# SMD.net
KiCad netlist of a schematic drawn in EAGLE
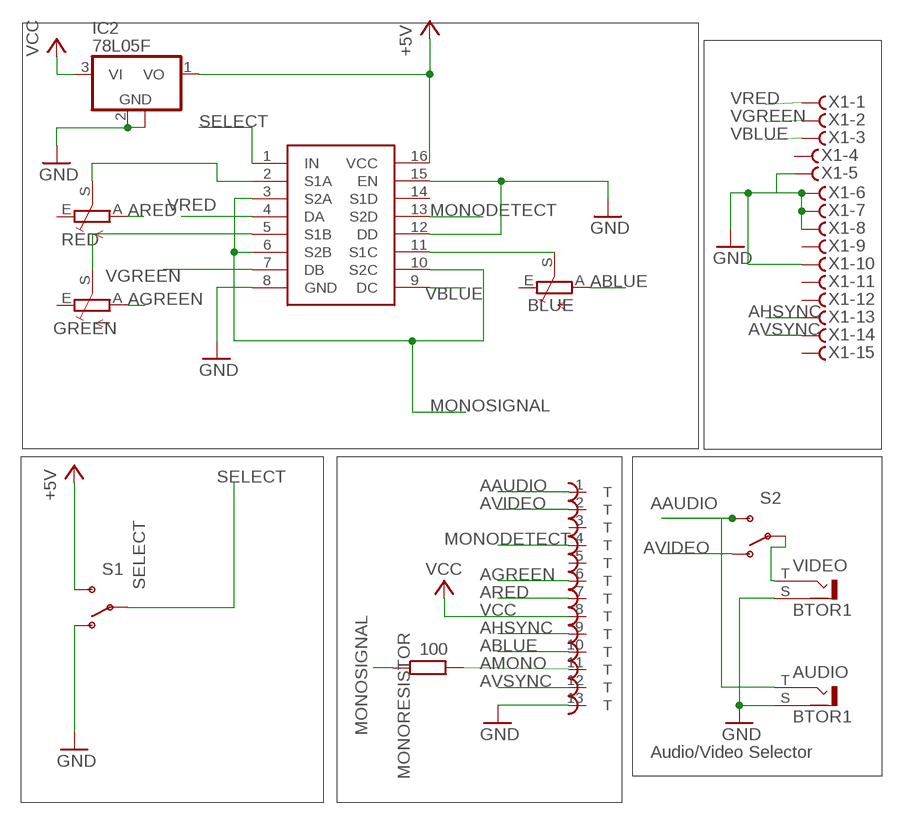
[diagram p0: schematic, sheet 1]

(export (version "E")
  (design (tool "Eeschema 10.0.6"))
  (components
    (comp (ref "ATARIOUT")
      (value "DIN13T")
      (footprint "eagle-import:ADADS")
      (libsource (lib "eagle-import") (part "DIN13T"))
    )
    (comp (ref "AUDIO")
      (value "BTOR1")
      (footprint "eagle-import:BTOR1")
      (libsource (lib "eagle-import") (part "BTOR1"))
    )
    (comp (ref "BLUE")
      (value "TRIM_EU-CA6H")
      (footprint "eagle-import:CA6H")
      (libsource (lib "eagle-import") (part "TRIM_EU-CA6H"))
    )
    (comp (ref "GREEN")
      (value "TRIM_EU-CA6H")
      (footprint "eagle-import:CA6H")
      (libsource (lib "eagle-import") (part "TRIM_EU-CA6H"))
    )
    (comp (ref "IC2")
      (value "78L05F")
      (footprint "eagle-import:SOT89")
      (libsource (lib "eagle-import") (part "78LF05"))
    )
    (comp (ref "MONORESISTOR")
      (value "100")
      (footprint "eagle-import:R1206")
      (libsource (lib "eagle-import") (part "R-EU_R1206"))
    )
    (comp (ref "RED")
      (value "TRIM_EU-CA6H")
      (footprint "eagle-import:CA6H")
      (libsource (lib "eagle-import") (part "TRIM_EU-CA6H"))
    )
    (comp (ref "S1")
      (value "SWITCH-SPDT-SMD-A")
      (footprint "eagle-import:SWITCH-SPST-SMD-A")
      (libsource (lib "eagle-import") (part "SWITCH-SPDT-SMD-A"))
    )
    (comp (ref "S2")
      (value "SWITCH-SPDT-SMD-A")
      (footprint "eagle-import:SWITCH-SPST-SMD-A")
      (libsource (lib "eagle-import") (part "SWITCH-SPDT-SMD-A"))
    )
    (comp (ref "TS5V330")
      (value "V330")
      (footprint "eagle-import:SOIC16N")
      (libsource (lib "eagle-import") (part "V330"))
    )
    (comp (ref "VIDEO")
      (value "BTOR1")
      (footprint "eagle-import:BTOR1")
      (libsource (lib "eagle-import") (part "BTOR1"))
    )
    (comp (ref "X1")
      (value "F15HDVS")
      (footprint "eagle-import:HDF15V")
      (libsource (lib "eagle-import") (part "F15?SHDV"))
    )
  )
  (nets
    (net (code "1") (name "+5V") (class "Default")
      (node (ref "IC2") (pin "1") (pinfunction "VO_1") (pintype "passive"))
      (node (ref "S1") (pin "3") (pinfunction "S_3") (pintype "passive"))
      (node (ref "TS5V330") (pin "16") (pinfunction "VCC_16") (pintype "bidirectional"))
    )
    (net (code "2") (name "/AAUDIO") (class "Default")
      (node (ref "ATARIOUT") (pin "1") (pinfunction "T_1") (pintype "passive"))
      (node (ref "AUDIO") (pin "T") (pinfunction "1_T") (pintype "passive"))
      (node (ref "S2") (pin "3") (pinfunction "S_3") (pintype "passive"))
    )
    (net (code "3") (name "/ABLUE") (class "Default")
      (node (ref "ATARIOUT") (pin "10") (pinfunction "T_10") (pintype "passive"))
      (node (ref "BLUE") (pin "A") (pinfunction "A_A") (pintype "passive"))
    )
    (net (code "4") (name "/AGREEN") (class "Default")
      (node (ref "ATARIOUT") (pin "6") (pinfunction "T_6") (pintype "passive"))
      (node (ref "GREEN") (pin "A") (pinfunction "A_A") (pintype "passive"))
    )
    (net (code "5") (name "/AHSYNC") (class "Default")
      (node (ref "ATARIOUT") (pin "9") (pinfunction "T_9") (pintype "passive"))
      (node (ref "X1") (pin "13") (pinfunction "F_13") (pintype "passive"))
    )
    (net (code "6") (name "/AMONO") (class "Default")
      (node (ref "ATARIOUT") (pin "11") (pinfunction "T_11") (pintype "passive"))
      (node (ref "MONORESISTOR") (pin "2") (pinfunction "2_2") (pintype "passive"))
    )
    (net (code "7") (name "/ARED") (class "Default")
      (node (ref "ATARIOUT") (pin "7") (pinfunction "T_7") (pintype "passive"))
      (node (ref "RED") (pin "A") (pinfunction "A_A") (pintype "passive"))
    )
    (net (code "8") (name "/AVIDEO") (class "Default")
      (node (ref "ATARIOUT") (pin "2") (pinfunction "T_2") (pintype "passive"))
      (node (ref "S2") (pin "1") (pinfunction "O_1") (pintype "passive"))
    )
    (net (code "9") (name "/AVSYNC") (class "Default")
      (node (ref "ATARIOUT") (pin "12") (pinfunction "T_12") (pintype "passive"))
      (node (ref "X1") (pin "14") (pinfunction "F_14") (pintype "passive"))
    )
    (net (code "10") (name "/MONODETECT") (class "Default")
      (node (ref "ATARIOUT") (pin "4") (pinfunction "T_4") (pintype "passive"))
      (node (ref "TS5V330") (pin "13") (pinfunction "S2D_13") (pintype "bidirectional"))
    )
    (net (code "11") (name "/MONOSIGNAL") (class "Default")
      (node (ref "MONORESISTOR") (pin "1") (pinfunction "1_1") (pintype "passive"))
      (node (ref "TS5V330") (pin "10") (pinfunction "S2C_10") (pintype "bidirectional"))
      (node (ref "TS5V330") (pin "3") (pinfunction "S2A_3") (pintype "bidirectional"))
      (node (ref "TS5V330") (pin "6") (pinfunction "S2B_6") (pintype "bidirectional"))
    )
    (net (code "12") (name "/SELECT") (class "Default")
      (node (ref "S1") (pin "2") (pinfunction "P_2") (pintype "passive"))
      (node (ref "TS5V330") (pin "1") (pinfunction "IN_1") (pintype "bidirectional"))
    )
    (net (code "13") (name "/VBLUE") (class "Default")
      (node (ref "TS5V330") (pin "9") (pinfunction "DC_9") (pintype "bidirectional"))
      (node (ref "X1") (pin "3") (pinfunction "F_3") (pintype "passive"))
    )
    (net (code "14") (name "/VGREEN") (class "Default")
      (node (ref "TS5V330") (pin "7") (pinfunction "DB_7") (pintype "bidirectional"))
      (node (ref "X1") (pin "2") (pinfunction "F_2") (pintype "passive"))
    )
    (net (code "15") (name "/VRED") (class "Default")
      (node (ref "TS5V330") (pin "4") (pinfunction "DA_4") (pintype "bidirectional"))
      (node (ref "X1") (pin "1") (pinfunction "F_1") (pintype "passive"))
    )
    (net (code "16") (name "GND") (class "Default")
      (node (ref "ATARIOUT") (pin "13") (pinfunction "T_13") (pintype "passive"))
      (node (ref "AUDIO") (pin "S") (pinfunction "2_S") (pintype "passive"))
      (node (ref "IC2") (pin "2") (pinfunction "GND_2") (pintype "passive"))
      (node (ref "IC2") (pin "2@1") (pinfunction "GND_2@1") (pintype "passive"))
      (node (ref "S1") (pin "1") (pinfunction "O_1") (pintype "passive"))
      (node (ref "TS5V330") (pin "12") (pinfunction "DD_12") (pintype "bidirectional"))
      (node (ref "TS5V330") (pin "15") (pinfunction "EN_15") (pintype "bidirectional"))
      (node (ref "TS5V330") (pin "8") (pinfunction "GND_8") (pintype "bidirectional"))
      (node (ref "VIDEO") (pin "S") (pinfunction "2_S") (pintype "passive"))
      (node (ref "X1") (pin "10") (pinfunction "F_10") (pintype "passive"))
      (node (ref "X1") (pin "5") (pinfunction "F_5") (pintype "passive"))
      (node (ref "X1") (pin "6") (pinfunction "F_6") (pintype "passive"))
      (node (ref "X1") (pin "7") (pinfunction "F_7") (pintype "passive"))
      (node (ref "X1") (pin "8") (pinfunction "F_8") (pintype "passive"))
    )
    (net (code "17") (name "Net-(S2-P)") (class "Default")
      (node (ref "S2") (pin "2") (pinfunction "P_2") (pintype "passive"))
      (node (ref "VIDEO") (pin "T") (pinfunction "1_T") (pintype "passive"))
    )
    (net (code "18") (name "Net-(TS5V330-S1A)") (class "Default")
      (node (ref "RED") (pin "S") (pinfunction "S_S") (pintype "passive"))
      (node (ref "TS5V330") (pin "2") (pinfunction "S1A_2") (pintype "bidirectional"))
    )
    (net (code "19") (name "Net-(TS5V330-S1B)") (class "Default")
      (node (ref "GREEN") (pin "S") (pinfunction "S_S") (pintype "passive"))
      (node (ref "TS5V330") (pin "5") (pinfunction "S1B_5") (pintype "bidirectional"))
    )
    (net (code "20") (name "Net-(TS5V330-S1C)") (class "Default")
      (node (ref "BLUE") (pin "S") (pinfunction "S_S") (pintype "passive"))
      (node (ref "TS5V330") (pin "11") (pinfunction "S1C_11") (pintype "bidirectional"))
    )
    (net (code "21") (name "VCC") (class "Default")
      (node (ref "ATARIOUT") (pin "8") (pinfunction "T_8") (pintype "passive"))
      (node (ref "IC2") (pin "3") (pinfunction "VI_3") (pintype "input"))
    )
    (net (code "22") (name "unconnected-(ATARIOUTG-T-Pad3)") (class "Default")
      (node (ref "ATARIOUT") (pin "3") (pinfunction "T_3") (pintype "passive"))
    )
    (net (code "23") (name "unconnected-(ATARIOUTI-T-Pad5)") (class "Default")
      (node (ref "ATARIOUT") (pin "5") (pinfunction "T_5") (pintype "passive"))
    )
    (net (code "24") (name "unconnected-(AUDIO-2-PadS@1)") (class "Default")
      (node (ref "AUDIO") (pin "S@1") (pinfunction "2_S@1") (pintype "passive"))
    )
    (net (code "25") (name "unconnected-(AUDIO-2-PadS@2)") (class "Default")
      (node (ref "AUDIO") (pin "S@2") (pinfunction "2_S@2") (pintype "passive"))
    )
    (net (code "26") (name "unconnected-(AUDIO-2-PadS@3)") (class "Default")
      (node (ref "AUDIO") (pin "S@3") (pinfunction "2_S@3") (pintype "passive"))
    )
    (net (code "27") (name "unconnected-(BLUE-PadE)") (class "Default")
      (node (ref "BLUE") (pin "E") (pinfunction "E_E") (pintype "passive"))
    )
    (net (code "28") (name "unconnected-(GREEN-PadE)") (class "Default")
      (node (ref "GREEN") (pin "E") (pinfunction "E_E") (pintype "passive"))
    )
    (net (code "29") (name "unconnected-(RED-PadE)") (class "Default")
      (node (ref "RED") (pin "E") (pinfunction "E_E") (pintype "passive"))
    )
    (net (code "30") (name "unconnected-(TS5V330-S1D-Pad14)") (class "Default")
      (node (ref "TS5V330") (pin "14") (pinfunction "S1D_14") (pintype "bidirectional"))
    )
    (net (code "31") (name "unconnected-(VIDEO-2-PadS@1)") (class "Default")
      (node (ref "VIDEO") (pin "S@1") (pinfunction "2_S@1") (pintype "passive"))
    )
    (net (code "32") (name "unconnected-(VIDEO-2-PadS@2)") (class "Default")
      (node (ref "VIDEO") (pin "S@2") (pinfunction "2_S@2") (pintype "passive"))
    )
    (net (code "33") (name "unconnected-(VIDEO-2-PadS@3)") (class "Default")
      (node (ref "VIDEO") (pin "S@3") (pinfunction "2_S@3") (pintype "passive"))
    )
    (net (code "34") (name "unconnected-(X1C-F-Pad11)") (class "Default")
      (node (ref "X1") (pin "11") (pinfunction "F_11") (pintype "passive"))
    )
    (net (code "35") (name "unconnected-(X1D-F-Pad12)") (class "Default")
      (node (ref "X1") (pin "12") (pinfunction "F_12") (pintype "passive"))
    )
    (net (code "36") (name "unconnected-(X1G-F-Pad15)") (class "Default")
      (node (ref "X1") (pin "15") (pinfunction "F_15") (pintype "passive"))
    )
    (net (code "37") (name "unconnected-(X1J-F-Pad4)") (class "Default")
      (node (ref "X1") (pin "4") (pinfunction "F_4") (pintype "passive"))
    )
    (net (code "38") (name "unconnected-(X1O-F-Pad9)") (class "Default")
      (node (ref "X1") (pin "9") (pinfunction "F_9") (pintype "passive"))
    )
  )
)
